# 9_USB_2_0.net
KiCad netlist of a schematic drawn in Altium Designer
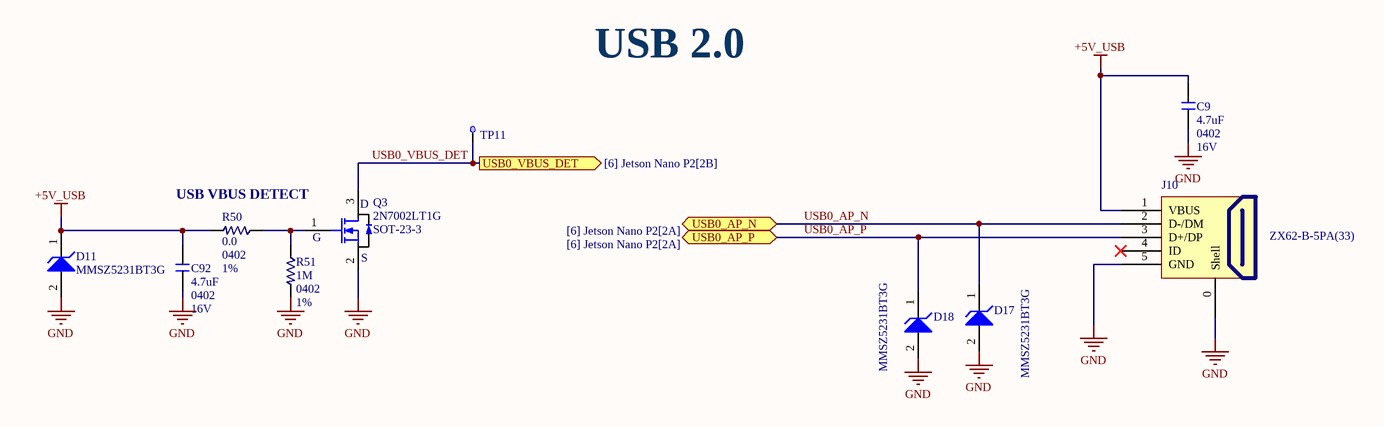
[diagram p0: [9] USB 2.0 .SchDoc]

(export (version "E")
  (design (tool "Eeschema 10.0.6"))
  (components
    (comp (ref "C9")
      (value "4.7uF")
      (footprint "C0402M")
      (description "CAP CER 4.7UF 16V X5R 0402")
      (fields
        (field (name "MANUFACTURER") "Samsung")
        (field (name "MANUFACTURER PART NUMBER") "CL05A475MO5NUNC")
        (field (name "CASE/PACKAGE") "0402")
        (field (name "VOLTAGE RATING") "16V")
      )
      (libsource (lib "CommonLib") (part "CAP_CER"))
    )
    (comp (ref "C92")
      (value "4.7uF")
      (footprint "C0402M")
      (description "CAP CER 4.7UF 16V X5R 0402")
      (fields
        (field (name "MANUFACTURER") "Samsung")
        (field (name "MANUFACTURER PART NUMBER") "CL05A475MO5NUNC")
        (field (name "CASE/PACKAGE") "0402")
        (field (name "VOLTAGE RATING") "16V")
      )
      (libsource (lib "CommonLib") (part "CAP_CER"))
    )
    (comp (ref "D11")
      (value "MMSZ5231BT3G")
      (footprint "SODFL371X135-2N")
      (description "DIODE ZENER 5.1V 500MW SOD123")
      (fields (field (name "MANUFACTURER") "ON Semiconductor") (field (name "TOLERANCE") "5%"))
      (libsource (lib "Eband") (part "MMSZ5231BT3G"))
    )
    (comp (ref "D17")
      (value "MMSZ5231BT3G")
      (footprint "SODFL371X135-2N")
      (description "DIODE ZENER 5.1V 500MW SOD123")
      (fields (field (name "MANUFACTURER") "ON Semiconductor") (field (name "TOLERANCE") "5%"))
      (libsource (lib "Eband") (part "MMSZ5231BT3G"))
    )
    (comp (ref "D18")
      (value "MMSZ5231BT3G")
      (footprint "SODFL371X135-2N")
      (description "DIODE ZENER 5.1V 500MW SOD123")
      (fields (field (name "MANUFACTURER") "ON Semiconductor") (field (name "TOLERANCE") "5%"))
      (libsource (lib "Eband") (part "MMSZ5231BT3G"))
    )
    (comp (ref "J10")
      (value "ZX62-B-5PA(33)")
      (footprint "MICRO-USB-SMD_5P-P0.65-H-M_MICRO-USB-5P")
      (description "USB - micro B USB 2.0 Receptacle Connector 5 Position Surface Mount, Right Angle")
      (fields (field (name "MANUFACTURER") "Hirose"))
      (libsource (lib "Schlib1") (part "USB Mini"))
    )
    (comp (ref "Q3")
      (value "2N7002LT1G")
      (footprint "SOT95P245X110-3N")
      (description "MOSFET N-CH 60V 0.115A SOT-23")
      (fields (field (name "MANUFACTURER") "ON Semiconductor") (field (name "CASE/PACKAGE") "SOT-23-3"))
      (libsource (lib "CommonLib") (part "NMOS"))
    )
    (comp (ref "R50")
      (value "0.0")
      (footprint "R0402M")
      (description "RES SMD 0 OHM JUMPER 1/16W 0402")
      (fields
        (field (name "MANUFACTURER") "Yageo")
        (field (name "MANUFACTURER PART NUMBER") "RC0402FR-070RL")
        (field (name "CASE CODE (IMPERIAL)") "0402")
        (field (name "TOLERANCE") "1%")
      )
      (libsource (lib "CommonLib") (part "RES_SMD"))
    )
    (comp (ref "R51")
      (value "1M")
      (footprint "R0402M")
      (description "RES SMD 1M OHM 1% 1/16W 0402")
      (fields
        (field (name "MANUFACTURER") "Yageo")
        (field (name "MANUFACTURER PART NUMBER") "RC0402FR-071ML")
        (field (name "CASE CODE (IMPERIAL)") "0402")
        (field (name "TOLERANCE") "1%")
      )
      (libsource (lib "CommonLib") (part "RES_SMD"))
    )
    (comp (ref "TP11")
      (value "TP")
      (footprint "Test point")
      (description "TESTPOINT")
      (libsource (lib "CommonLib") (part "TestPoint"))
    )
  )
  (nets
    (net (code "1") (name "+5V_USB") (class "Default")
      (node (ref "C9") (pin "1") (pinfunction "1_1") (pintype "passive"))
      (node (ref "C92") (pin "1") (pinfunction "1_1") (pintype "passive"))
      (node (ref "D11") (pin "1") (pinfunction "K_1") (pintype "passive"))
      (node (ref "J10") (pin "1") (pinfunction "VBUS_1") (pintype "passive"))
      (node (ref "R50") (pin "1") (pinfunction "1_1") (pintype "passive"))
    )
    (net (code "2") (name "/USB0_AP_N") (class "Default")
      (node (ref "D17") (pin "1") (pinfunction "K_1") (pintype "passive"))
      (node (ref "J10") (pin "2") (pinfunction "D-/DM_2") (pintype "passive"))
    )
    (net (code "3") (name "/USB0_AP_P") (class "Default")
      (node (ref "D18") (pin "1") (pinfunction "K_1") (pintype "passive"))
      (node (ref "J10") (pin "3") (pinfunction "D+/DP_3") (pintype "passive"))
    )
    (net (code "4") (name "/USB0_VBUS_DET") (class "Default")
      (node (ref "Q3") (pin "3") (pinfunction "D_3") (pintype "passive"))
      (node (ref "TP11") (pin "1") (pinfunction "TP_1") (pintype "passive"))
    )
    (net (code "5") (name "GND") (class "Default")
      (node (ref "C9") (pin "2") (pinfunction "2_2") (pintype "passive"))
      (node (ref "C92") (pin "2") (pinfunction "2_2") (pintype "passive"))
      (node (ref "D11") (pin "2") (pinfunction "A_2") (pintype "passive"))
      (node (ref "D17") (pin "2") (pinfunction "A_2") (pintype "passive"))
      (node (ref "D18") (pin "2") (pinfunction "A_2") (pintype "passive"))
      (node (ref "J10") (pin "0") (pinfunction "Shell_0") (pintype "passive"))
      (node (ref "J10") (pin "5") (pinfunction "GND_5") (pintype "passive"))
      (node (ref "Q3") (pin "2") (pinfunction "S_2") (pintype "passive"))
      (node (ref "R51") (pin "1") (pinfunction "1_1") (pintype "passive"))
    )
    (net (code "6") (name "Net-(Q3-G)") (class "Default")
      (node (ref "Q3") (pin "1") (pinfunction "G_1") (pintype "passive"))
      (node (ref "R50") (pin "2") (pinfunction "2_2") (pintype "passive"))
      (node (ref "R51") (pin "2") (pinfunction "2_2") (pintype "passive"))
    )
    (net (code "7") (name "unconnected-(J10-ID-Pad4)") (class "Default")
      (node (ref "J10") (pin "4") (pinfunction "ID_4") (pintype "passive+no_connect"))
    )
  )
)
